# Engi301_Project_Schematic.net
KiCad netlist of a schematic drawn in EAGLE
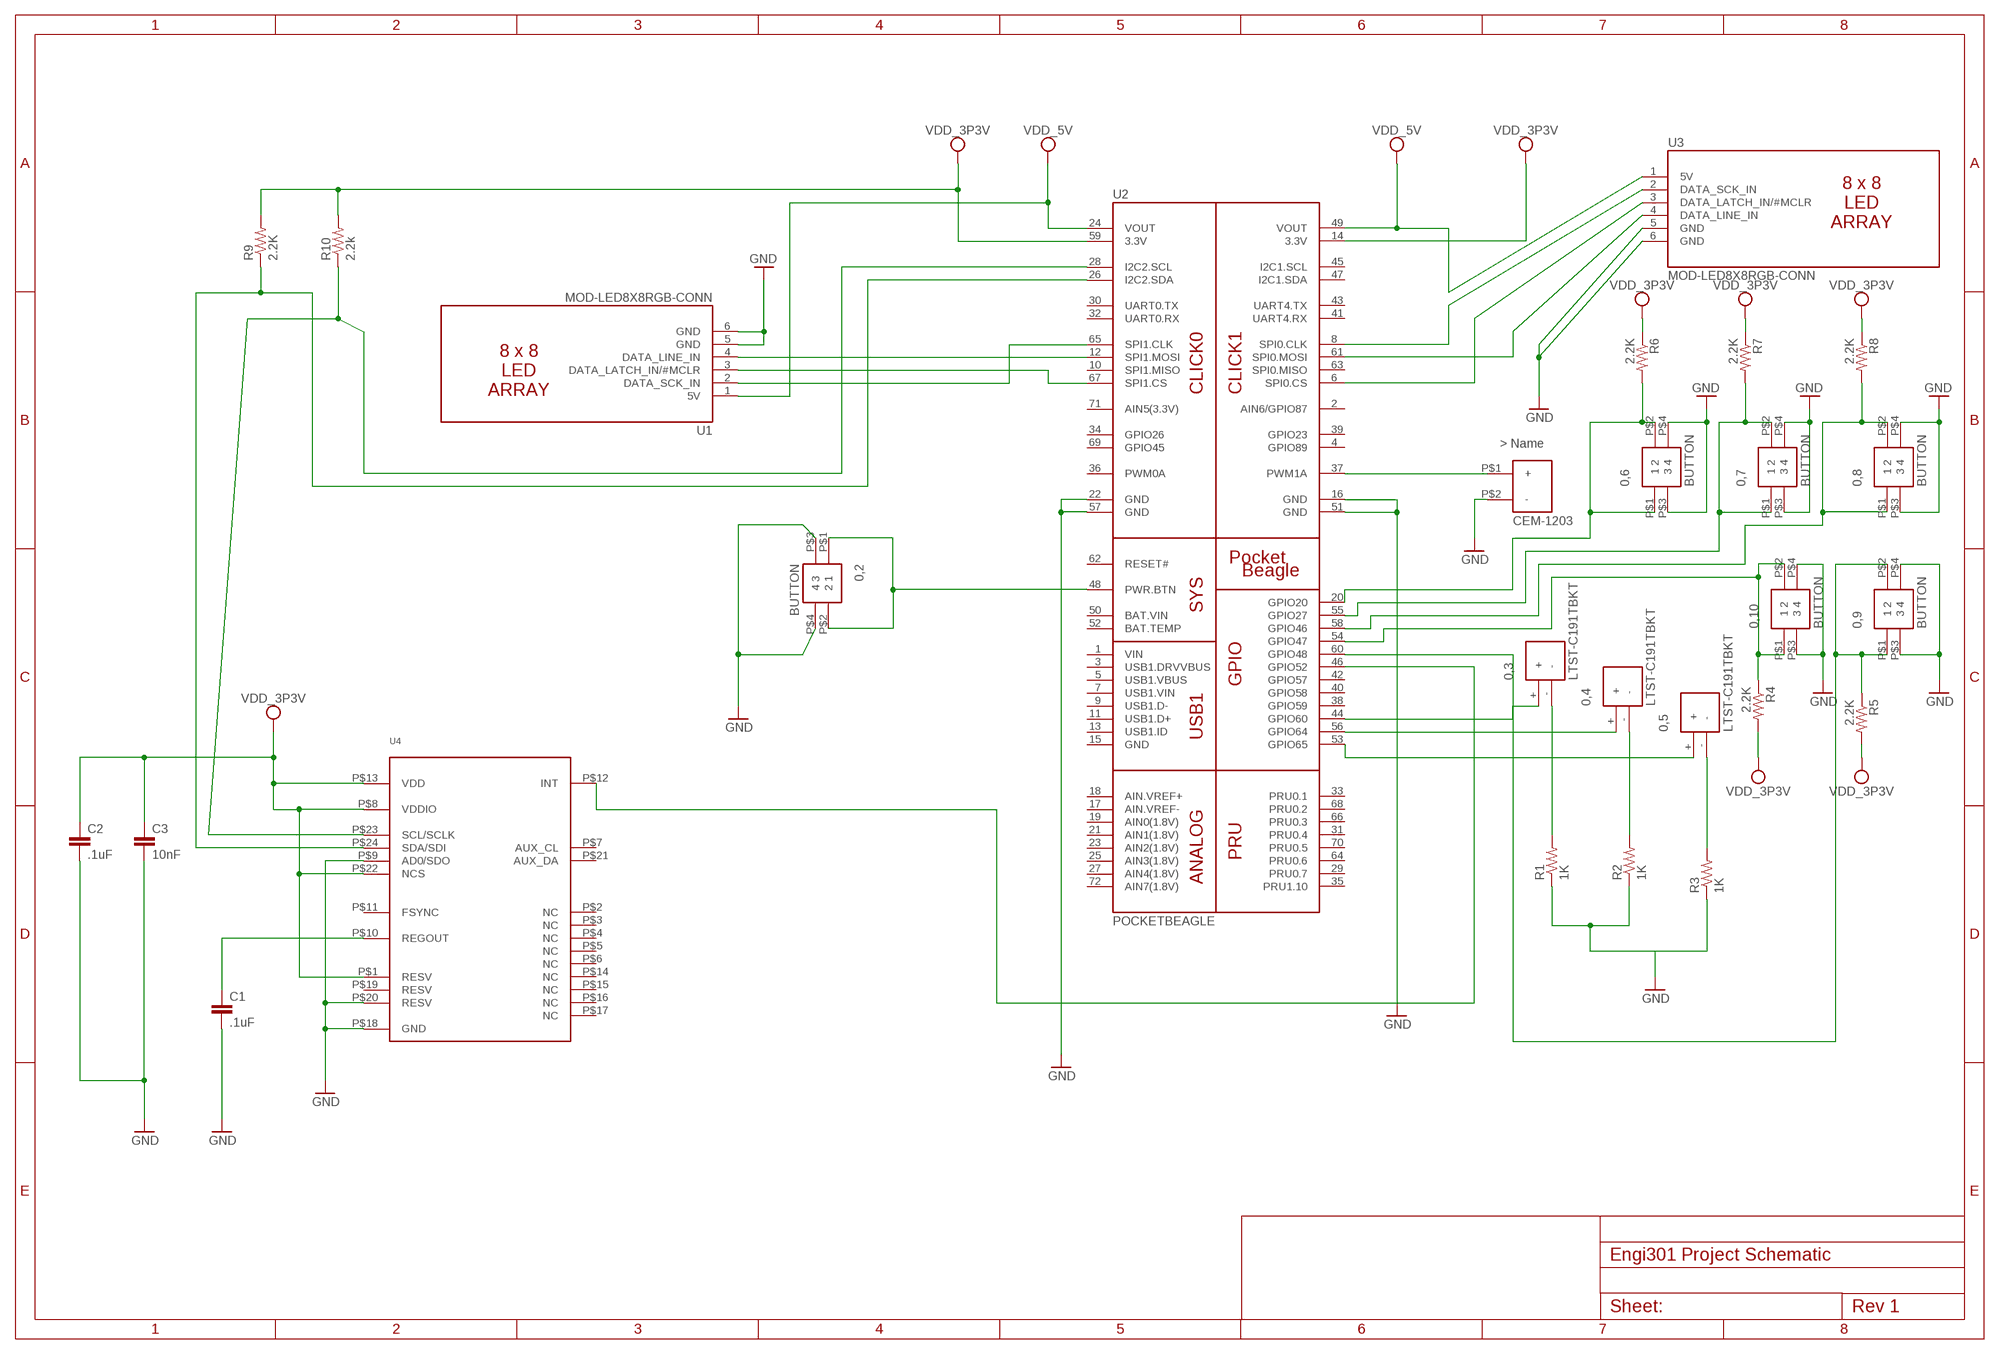
[diagram p0: schematic, sheet 1]

(export (version "E")
  (design (tool "Eeschema 10.0.6"))
  (components
    (comp (ref "0,1")
      (value "CEM-1203")
      (footprint "eagle-import:CEM-1203")
      (libsource (lib "eagle-import") (part "CEM-1203"))
    )
    (comp (ref "0,2")
      (value "BUTTON")
      (footprint "eagle-import:BUTTON")
      (libsource (lib "eagle-import") (part "BUTTON"))
    )
    (comp (ref "0,3")
      (value "LTST-C191TBKT")
      (footprint "eagle-import:LTST_C191TBKT")
      (libsource (lib "eagle-import") (part "LTST-C191TBKT"))
    )
    (comp (ref "0,4")
      (value "LTST-C191TBKT")
      (footprint "eagle-import:LTST_C191TBKT")
      (libsource (lib "eagle-import") (part "LTST-C191TBKT"))
    )
    (comp (ref "0,5")
      (value "LTST-C191TBKT")
      (footprint "eagle-import:LTST_C191TBKT")
      (libsource (lib "eagle-import") (part "LTST-C191TBKT"))
    )
    (comp (ref "0,6")
      (value "BUTTON")
      (footprint "eagle-import:BUTTON")
      (libsource (lib "eagle-import") (part "BUTTON"))
    )
    (comp (ref "0,7")
      (value "BUTTON")
      (footprint "eagle-import:BUTTON")
      (libsource (lib "eagle-import") (part "BUTTON"))
    )
    (comp (ref "0,8")
      (value "BUTTON")
      (footprint "eagle-import:BUTTON")
      (libsource (lib "eagle-import") (part "BUTTON"))
    )
    (comp (ref "0,9")
      (value "BUTTON")
      (footprint "eagle-import:BUTTON")
      (libsource (lib "eagle-import") (part "BUTTON"))
    )
    (comp (ref "0,10")
      (value "BUTTON")
      (footprint "eagle-import:BUTTON")
      (libsource (lib "eagle-import") (part "BUTTON"))
    )
    (comp (ref "C1")
      (value ".1uF")
      (footprint "eagle-import:C0603")
      (libsource (lib "eagle-import") (part "C_C0603"))
    )
    (comp (ref "C2")
      (value ".1uF")
      (footprint "eagle-import:C0603")
      (libsource (lib "eagle-import") (part "C_C0603"))
    )
    (comp (ref "C3")
      (value "10nF")
      (footprint "eagle-import:C0402")
      (libsource (lib "eagle-import") (part "C_C0402"))
    )
    (comp (ref "R1")
      (value "1K")
      (footprint "eagle-import:R0603")
      (libsource (lib "eagle-import") (part "R_R0603"))
    )
    (comp (ref "R2")
      (value "1K")
      (footprint "eagle-import:R0603")
      (libsource (lib "eagle-import") (part "R_R0603"))
    )
    (comp (ref "R3")
      (value "1K")
      (footprint "eagle-import:R0603")
      (libsource (lib "eagle-import") (part "R_R0603"))
    )
    (comp (ref "R4")
      (value "2.2K")
      (footprint "eagle-import:R0603")
      (libsource (lib "eagle-import") (part "R_R0603"))
    )
    (comp (ref "R5")
      (value "2.2K")
      (footprint "eagle-import:R0603")
      (libsource (lib "eagle-import") (part "R_R0603"))
    )
    (comp (ref "R6")
      (value "2.2K")
      (footprint "eagle-import:R0603")
      (libsource (lib "eagle-import") (part "R_R0603"))
    )
    (comp (ref "R7")
      (value "2.2K")
      (footprint "eagle-import:R0603")
      (libsource (lib "eagle-import") (part "R_R0603"))
    )
    (comp (ref "R8")
      (value "2.2K")
      (footprint "eagle-import:R0603")
      (libsource (lib "eagle-import") (part "R_R0603"))
    )
    (comp (ref "R9")
      (value "2.2K")
      (footprint "eagle-import:R0603")
      (libsource (lib "eagle-import") (part "R_R0603"))
    )
    (comp (ref "R10")
      (value "2.2k")
      (footprint "eagle-import:R0603")
      (libsource (lib "eagle-import") (part "R_R0603"))
    )
    (comp (ref "U1")
      (value "MOD-LED8X8RGB-CONN")
      (footprint "eagle-import:FE06W")
      (libsource (lib "eagle-import") (part "MOD-LED8X8RGB-CONN"))
    )
    (comp (ref "U2")
      (value "POCKETBEAGLE")
      (footprint "eagle-import:POCKETBEAGLE")
      (libsource (lib "eagle-import") (part "POCKETBEAGLE"))
    )
    (comp (ref "U3")
      (value "MOD-LED8X8RGB-CONN")
      (footprint "eagle-import:FE06W")
      (libsource (lib "eagle-import") (part "MOD-LED8X8RGB-CONN"))
    )
    (comp (ref "U4")
      (value "MPU-9250")
      (footprint "eagle-import:QFN_3MMX3MM")
      (libsource (lib "eagle-import") (part "MPU-9250"))
    )
  )
  (nets
    (net (code "1") (name "GND") (class "Default")
      (node (ref "0,1") (pin "P$2") (pinfunction "-_P$2") (pintype "bidirectional"))
      (node (ref "0,10") (pin "P$3") (pinfunction "3_P$3") (pintype "bidirectional"))
      (node (ref "0,10") (pin "P$4") (pinfunction "4_P$4") (pintype "bidirectional"))
      (node (ref "0,2") (pin "P$3") (pinfunction "3_P$3") (pintype "bidirectional"))
      (node (ref "0,2") (pin "P$4") (pinfunction "4_P$4") (pintype "bidirectional"))
      (node (ref "0,6") (pin "P$3") (pinfunction "3_P$3") (pintype "bidirectional"))
      (node (ref "0,6") (pin "P$4") (pinfunction "4_P$4") (pintype "bidirectional"))
      (node (ref "0,7") (pin "P$3") (pinfunction "3_P$3") (pintype "bidirectional"))
      (node (ref "0,7") (pin "P$4") (pinfunction "4_P$4") (pintype "bidirectional"))
      (node (ref "0,8") (pin "P$3") (pinfunction "3_P$3") (pintype "bidirectional"))
      (node (ref "0,8") (pin "P$4") (pinfunction "4_P$4") (pintype "bidirectional"))
      (node (ref "0,9") (pin "P$3") (pinfunction "3_P$3") (pintype "bidirectional"))
      (node (ref "0,9") (pin "P$4") (pinfunction "4_P$4") (pintype "bidirectional"))
      (node (ref "C1") (pin "2") (pinfunction "2_2") (pintype "passive"))
      (node (ref "C2") (pin "2") (pinfunction "2_2") (pintype "passive"))
      (node (ref "C3") (pin "2") (pinfunction "2_2") (pintype "passive"))
      (node (ref "R1") (pin "1") (pinfunction "1_1") (pintype "passive"))
      (node (ref "R2") (pin "1") (pinfunction "1_1") (pintype "passive"))
      (node (ref "R3") (pin "1") (pinfunction "1_1") (pintype "passive"))
      (node (ref "U1") (pin "5") (pinfunction "GND_5") (pintype "bidirectional"))
      (node (ref "U1") (pin "6") (pinfunction "GND_6") (pintype "bidirectional"))
      (node (ref "U2") (pin "16") (pinfunction "GND_16") (pintype "bidirectional"))
      (node (ref "U2") (pin "22") (pinfunction "GND_22") (pintype "bidirectional"))
      (node (ref "U2") (pin "51") (pinfunction "GND_51") (pintype "bidirectional"))
      (node (ref "U2") (pin "57") (pinfunction "GND_57") (pintype "bidirectional"))
      (node (ref "U3") (pin "5") (pinfunction "GND_5") (pintype "bidirectional"))
      (node (ref "U3") (pin "6") (pinfunction "GND_6") (pintype "bidirectional"))
      (node (ref "U4") (pin "P$18") (pinfunction "GND_P$18") (pintype "bidirectional"))
      (node (ref "U4") (pin "P$20") (pinfunction "RESV_P$20") (pintype "bidirectional"))
      (node (ref "U4") (pin "P$9") (pinfunction "AD0/SDO_P$9") (pintype "bidirectional"))
    )
    (net (code "2") (name "Net-(0,1-+)") (class "Default")
      (node (ref "0,1") (pin "P$1") (pinfunction "+_P$1") (pintype "bidirectional"))
      (node (ref "U2") (pin "37") (pinfunction "PWM1A_37") (pintype "bidirectional"))
    )
    (net (code "3") (name "Net-(0,2-1)") (class "Default")
      (node (ref "0,2") (pin "P$1") (pinfunction "1_P$1") (pintype "bidirectional"))
      (node (ref "0,2") (pin "P$2") (pinfunction "2_P$2") (pintype "bidirectional"))
      (node (ref "U2") (pin "48") (pinfunction "PWR.BTN_48") (pintype "bidirectional"))
    )
    (net (code "4") (name "Net-(0,3-Pad-)") (class "Default")
      (node (ref "0,3") (pin "-") (pinfunction "-_-") (pintype "bidirectional"))
      (node (ref "R1") (pin "2") (pinfunction "2_2") (pintype "passive"))
    )
    (net (code "5") (name "Net-(0,4-Pad-)") (class "Default")
      (node (ref "0,4") (pin "-") (pinfunction "-_-") (pintype "bidirectional"))
      (node (ref "R2") (pin "2") (pinfunction "2_2") (pintype "passive"))
    )
    (net (code "6") (name "Net-(0,5-Pad-)") (class "Default")
      (node (ref "0,5") (pin "-") (pinfunction "-_-") (pintype "bidirectional"))
      (node (ref "R3") (pin "2") (pinfunction "2_2") (pintype "passive"))
    )
    (net (code "7") (name "Net-(0,6-1)") (class "Default")
      (node (ref "0,6") (pin "P$1") (pinfunction "1_P$1") (pintype "bidirectional"))
      (node (ref "0,6") (pin "P$2") (pinfunction "2_P$2") (pintype "bidirectional"))
      (node (ref "R6") (pin "2") (pinfunction "2_2") (pintype "passive"))
      (node (ref "U2") (pin "20") (pinfunction "GPIO20_20") (pintype "bidirectional"))
    )
    (net (code "8") (name "Net-(0,7-1)") (class "Default")
      (node (ref "0,7") (pin "P$1") (pinfunction "1_P$1") (pintype "bidirectional"))
      (node (ref "0,7") (pin "P$2") (pinfunction "2_P$2") (pintype "bidirectional"))
      (node (ref "R7") (pin "2") (pinfunction "2_2") (pintype "passive"))
      (node (ref "U2") (pin "55") (pinfunction "GPIO27_55") (pintype "bidirectional"))
    )
    (net (code "9") (name "Net-(0,8-1)") (class "Default")
      (node (ref "0,8") (pin "P$1") (pinfunction "1_P$1") (pintype "bidirectional"))
      (node (ref "0,8") (pin "P$2") (pinfunction "2_P$2") (pintype "bidirectional"))
      (node (ref "R8") (pin "2") (pinfunction "2_2") (pintype "passive"))
      (node (ref "U2") (pin "58") (pinfunction "GPIO46_58") (pintype "bidirectional"))
    )
    (net (code "10") (name "Net-(0,9-1)") (class "Default")
      (node (ref "0,9") (pin "P$1") (pinfunction "1_P$1") (pintype "bidirectional"))
      (node (ref "0,9") (pin "P$2") (pinfunction "2_P$2") (pintype "bidirectional"))
      (node (ref "R5") (pin "1") (pinfunction "1_1") (pintype "passive"))
      (node (ref "U2") (pin "60") (pinfunction "GPIO48_60") (pintype "bidirectional"))
    )
    (net (code "11") (name "Net-(0,10-1)") (class "Default")
      (node (ref "0,10") (pin "P$1") (pinfunction "1_P$1") (pintype "bidirectional"))
      (node (ref "0,10") (pin "P$2") (pinfunction "2_P$2") (pintype "bidirectional"))
      (node (ref "R4") (pin "1") (pinfunction "1_1") (pintype "passive"))
      (node (ref "U2") (pin "54") (pinfunction "GPIO47_54") (pintype "bidirectional"))
    )
    (net (code "12") (name "Net-(U1-DATA_LATCH_IN{slash}#MCLR)") (class "Default")
      (node (ref "U1") (pin "3") (pinfunction "DATA_LATCH_IN/#MCLR_3") (pintype "bidirectional"))
      (node (ref "U2") (pin "67") (pinfunction "SPI1.CS_67") (pintype "bidirectional"))
    )
    (net (code "13") (name "Net-(U1-DATA_LINE_IN)") (class "Default")
      (node (ref "U1") (pin "4") (pinfunction "DATA_LINE_IN_4") (pintype "bidirectional"))
      (node (ref "U2") (pin "12") (pinfunction "SPI1.MOSI_12") (pintype "bidirectional"))
    )
    (net (code "14") (name "Net-(U1-DATA_SCK_IN)") (class "Default")
      (node (ref "U1") (pin "2") (pinfunction "DATA_SCK_IN_2") (pintype "bidirectional"))
      (node (ref "U2") (pin "65") (pinfunction "SPI1.CLK_65") (pintype "bidirectional"))
    )
    (net (code "15") (name "Net-(U2-GPIO52)") (class "Default")
      (node (ref "U2") (pin "46") (pinfunction "GPIO52_46") (pintype "bidirectional"))
      (node (ref "U4") (pin "P$12") (pinfunction "INT_P$12") (pintype "bidirectional"))
    )
    (net (code "16") (name "Net-(U2-GPIO60)") (class "Default")
      (node (ref "0,3") (pin "+") (pinfunction "+_+") (pintype "bidirectional"))
      (node (ref "U2") (pin "44") (pinfunction "GPIO60_44") (pintype "bidirectional"))
    )
    (net (code "17") (name "Net-(U2-GPIO64)") (class "Default")
      (node (ref "0,4") (pin "+") (pinfunction "+_+") (pintype "bidirectional"))
      (node (ref "U2") (pin "56") (pinfunction "GPIO64_56") (pintype "bidirectional"))
    )
    (net (code "18") (name "Net-(U2-GPIO65)") (class "Default")
      (node (ref "0,5") (pin "+") (pinfunction "+_+") (pintype "bidirectional"))
      (node (ref "U2") (pin "53") (pinfunction "GPIO65_53") (pintype "bidirectional"))
    )
    (net (code "19") (name "Net-(U2-I2C2.SCL)") (class "Default")
      (node (ref "R10") (pin "1") (pinfunction "1_1") (pintype "passive"))
      (node (ref "U2") (pin "28") (pinfunction "I2C2.SCL_28") (pintype "bidirectional"))
      (node (ref "U4") (pin "P$23") (pinfunction "SCL/SCLK_P$23") (pintype "bidirectional"))
    )
    (net (code "20") (name "Net-(U2-I2C2.SDA)") (class "Default")
      (node (ref "R9") (pin "1") (pinfunction "1_1") (pintype "passive"))
      (node (ref "U2") (pin "26") (pinfunction "I2C2.SDA_26") (pintype "bidirectional"))
      (node (ref "U4") (pin "P$24") (pinfunction "SDA/SDI_P$24") (pintype "bidirectional"))
    )
    (net (code "21") (name "Net-(U2-SPI0.CLK)") (class "Default")
      (node (ref "U2") (pin "8") (pinfunction "SPI0.CLK_8") (pintype "bidirectional"))
      (node (ref "U3") (pin "2") (pinfunction "DATA_SCK_IN_2") (pintype "bidirectional"))
    )
    (net (code "22") (name "Net-(U2-SPI0.CS)") (class "Default")
      (node (ref "U2") (pin "6") (pinfunction "SPI0.CS_6") (pintype "bidirectional"))
      (node (ref "U3") (pin "3") (pinfunction "DATA_LATCH_IN/#MCLR_3") (pintype "bidirectional"))
    )
    (net (code "23") (name "Net-(U2-SPI0.MOSI)") (class "Default")
      (node (ref "U2") (pin "61") (pinfunction "SPI0.MOSI_61") (pintype "bidirectional"))
      (node (ref "U3") (pin "4") (pinfunction "DATA_LINE_IN_4") (pintype "bidirectional"))
    )
    (net (code "24") (name "Net-(U4-REGOUT)") (class "Default")
      (node (ref "C1") (pin "1") (pinfunction "1_1") (pintype "passive"))
      (node (ref "U4") (pin "P$10") (pinfunction "REGOUT_P$10") (pintype "bidirectional"))
    )
    (net (code "25") (name "VDD_3P3V") (class "Default")
      (node (ref "C2") (pin "1") (pinfunction "1_1") (pintype "passive"))
      (node (ref "C3") (pin "1") (pinfunction "1_1") (pintype "passive"))
      (node (ref "R10") (pin "2") (pinfunction "2_2") (pintype "passive"))
      (node (ref "R4") (pin "2") (pinfunction "2_2") (pintype "passive"))
      (node (ref "R5") (pin "2") (pinfunction "2_2") (pintype "passive"))
      (node (ref "R6") (pin "1") (pinfunction "1_1") (pintype "passive"))
      (node (ref "R7") (pin "1") (pinfunction "1_1") (pintype "passive"))
      (node (ref "R8") (pin "1") (pinfunction "1_1") (pintype "passive"))
      (node (ref "R9") (pin "2") (pinfunction "2_2") (pintype "passive"))
      (node (ref "U2") (pin "14") (pinfunction "3.3V_14") (pintype "bidirectional"))
      (node (ref "U2") (pin "59") (pinfunction "3.3V_59") (pintype "bidirectional"))
      (node (ref "U4") (pin "P$1") (pinfunction "RESV_P$1") (pintype "bidirectional"))
      (node (ref "U4") (pin "P$13") (pinfunction "VDD_P$13") (pintype "bidirectional"))
      (node (ref "U4") (pin "P$22") (pinfunction "NCS_P$22") (pintype "bidirectional"))
      (node (ref "U4") (pin "P$8") (pinfunction "VDDIO_P$8") (pintype "bidirectional"))
    )
    (net (code "26") (name "VDD_5V") (class "Default")
      (node (ref "U1") (pin "1") (pinfunction "5V_1") (pintype "bidirectional"))
      (node (ref "U2") (pin "24") (pinfunction "VOUT_24") (pintype "bidirectional"))
      (node (ref "U2") (pin "49") (pinfunction "VOUT_49") (pintype "bidirectional"))
      (node (ref "U3") (pin "1") (pinfunction "5V_1") (pintype "bidirectional"))
    )
    (net (code "27") (name "unconnected-(U2-AIN.VREF+-Pad18)") (class "Default")
      (node (ref "U2") (pin "18") (pinfunction "AIN.VREF+_18") (pintype "bidirectional"))
    )
    (net (code "28") (name "unconnected-(U2-AIN.VREF--Pad17)") (class "Default")
      (node (ref "U2") (pin "17") (pinfunction "AIN.VREF-_17") (pintype "bidirectional"))
    )
    (net (code "29") (name "unconnected-(U2-AIN0(1.8V)-Pad19)") (class "Default")
      (node (ref "U2") (pin "19") (pinfunction "AIN0(1.8V)_19") (pintype "bidirectional"))
    )
    (net (code "30") (name "unconnected-(U2-AIN1(1.8V)-Pad21)") (class "Default")
      (node (ref "U2") (pin "21") (pinfunction "AIN1(1.8V)_21") (pintype "bidirectional"))
    )
    (net (code "31") (name "unconnected-(U2-AIN2(1.8V)-Pad23)") (class "Default")
      (node (ref "U2") (pin "23") (pinfunction "AIN2(1.8V)_23") (pintype "bidirectional"))
    )
    (net (code "32") (name "unconnected-(U2-AIN3(1.8V)-Pad25)") (class "Default")
      (node (ref "U2") (pin "25") (pinfunction "AIN3(1.8V)_25") (pintype "bidirectional"))
    )
    (net (code "33") (name "unconnected-(U2-AIN4(1.8V)-Pad27)") (class "Default")
      (node (ref "U2") (pin "27") (pinfunction "AIN4(1.8V)_27") (pintype "bidirectional"))
    )
    (net (code "34") (name "unconnected-(U2-AIN5(3.3V)-Pad71)") (class "Default")
      (node (ref "U2") (pin "71") (pinfunction "AIN5(3.3V)_71") (pintype "bidirectional"))
    )
    (net (code "35") (name "unconnected-(U2-AIN6{slash}GPIO87-Pad2)") (class "Default")
      (node (ref "U2") (pin "2") (pinfunction "AIN6/GPIO87_2") (pintype "bidirectional"))
    )
    (net (code "36") (name "unconnected-(U2-AIN7(1.8V)-Pad72)") (class "Default")
      (node (ref "U2") (pin "72") (pinfunction "AIN7(1.8V)_72") (pintype "bidirectional"))
    )
    (net (code "37") (name "unconnected-(U2-BAT.TEMP-Pad52)") (class "Default")
      (node (ref "U2") (pin "52") (pinfunction "BAT.TEMP_52") (pintype "bidirectional"))
    )
    (net (code "38") (name "unconnected-(U2-BAT.VIN-Pad50)") (class "Default")
      (node (ref "U2") (pin "50") (pinfunction "BAT.VIN_50") (pintype "bidirectional"))
    )
    (net (code "39") (name "unconnected-(U2-GND-Pad15)") (class "Default")
      (node (ref "U2") (pin "15") (pinfunction "GND_15") (pintype "bidirectional"))
    )
    (net (code "40") (name "unconnected-(U2-GPIO23-Pad39)") (class "Default")
      (node (ref "U2") (pin "39") (pinfunction "GPIO23_39") (pintype "bidirectional"))
    )
    (net (code "41") (name "unconnected-(U2-GPIO26-Pad34)") (class "Default")
      (node (ref "U2") (pin "34") (pinfunction "GPIO26_34") (pintype "bidirectional"))
    )
    (net (code "42") (name "unconnected-(U2-GPIO45-Pad69)") (class "Default")
      (node (ref "U2") (pin "69") (pinfunction "GPIO45_69") (pintype "bidirectional"))
    )
    (net (code "43") (name "unconnected-(U2-GPIO57-Pad42)") (class "Default")
      (node (ref "U2") (pin "42") (pinfunction "GPIO57_42") (pintype "bidirectional"))
    )
    (net (code "44") (name "unconnected-(U2-GPIO58-Pad40)") (class "Default")
      (node (ref "U2") (pin "40") (pinfunction "GPIO58_40") (pintype "bidirectional"))
    )
    (net (code "45") (name "unconnected-(U2-GPIO59-Pad38)") (class "Default")
      (node (ref "U2") (pin "38") (pinfunction "GPIO59_38") (pintype "bidirectional"))
    )
    (net (code "46") (name "unconnected-(U2-GPIO89-Pad4)") (class "Default")
      (node (ref "U2") (pin "4") (pinfunction "GPIO89_4") (pintype "bidirectional"))
    )
    (net (code "47") (name "unconnected-(U2-I2C1.SCL-Pad45)") (class "Default")
      (node (ref "U2") (pin "45") (pinfunction "I2C1.SCL_45") (pintype "bidirectional"))
    )
    (net (code "48") (name "unconnected-(U2-I2C1.SDA-Pad47)") (class "Default")
      (node (ref "U2") (pin "47") (pinfunction "I2C1.SDA_47") (pintype "bidirectional"))
    )
    (net (code "49") (name "unconnected-(U2-PRU0.1-Pad33)") (class "Default")
      (node (ref "U2") (pin "33") (pinfunction "PRU0.1_33") (pintype "bidirectional"))
    )
    (net (code "50") (name "unconnected-(U2-PRU0.2-Pad68)") (class "Default")
      (node (ref "U2") (pin "68") (pinfunction "PRU0.2_68") (pintype "bidirectional"))
    )
    (net (code "51") (name "unconnected-(U2-PRU0.3-Pad66)") (class "Default")
      (node (ref "U2") (pin "66") (pinfunction "PRU0.3_66") (pintype "bidirectional"))
    )
    (net (code "52") (name "unconnected-(U2-PRU0.4-Pad31)") (class "Default")
      (node (ref "U2") (pin "31") (pinfunction "PRU0.4_31") (pintype "bidirectional"))
    )
    (net (code "53") (name "unconnected-(U2-PRU0.5-Pad70)") (class "Default")
      (node (ref "U2") (pin "70") (pinfunction "PRU0.5_70") (pintype "bidirectional"))
    )
    (net (code "54") (name "unconnected-(U2-PRU0.6-Pad64)") (class "Default")
      (node (ref "U2") (pin "64") (pinfunction "PRU0.6_64") (pintype "bidirectional"))
    )
    (net (code "55") (name "unconnected-(U2-PRU0.7-Pad29)") (class "Default")
      (node (ref "U2") (pin "29") (pinfunction "PRU0.7_29") (pintype "bidirectional"))
    )
    (net (code "56") (name "unconnected-(U2-PRU1.10-Pad35)") (class "Default")
      (node (ref "U2") (pin "35") (pinfunction "PRU1.10_35") (pintype "bidirectional"))
    )
    (net (code "57") (name "unconnected-(U2-PWM0A-Pad36)") (class "Default")
      (node (ref "U2") (pin "36") (pinfunction "PWM0A_36") (pintype "bidirectional"))
    )
    (net (code "58") (name "unconnected-(U2-RESET#-Pad62)") (class "Default")
      (node (ref "U2") (pin "62") (pinfunction "RESET#_62") (pintype "bidirectional"))
    )
    (net (code "59") (name "unconnected-(U2-SPI0.MISO-Pad63)") (class "Default")
      (node (ref "U2") (pin "63") (pinfunction "SPI0.MISO_63") (pintype "bidirectional"))
    )
    (net (code "60") (name "unconnected-(U2-SPI1.MISO-Pad10)") (class "Default")
      (node (ref "U2") (pin "10") (pinfunction "SPI1.MISO_10") (pintype "bidirectional"))
    )
    (net (code "61") (name "unconnected-(U2-UART0.RX-Pad32)") (class "Default")
      (node (ref "U2") (pin "32") (pinfunction "UART0.RX_32") (pintype "bidirectional"))
    )
    (net (code "62") (name "unconnected-(U2-UART0.TX-Pad30)") (class "Default")
      (node (ref "U2") (pin "30") (pinfunction "UART0.TX_30") (pintype "bidirectional"))
    )
    (net (code "63") (name "unconnected-(U2-UART4.RX-Pad41)") (class "Default")
      (node (ref "U2") (pin "41") (pinfunction "UART4.RX_41") (pintype "bidirectional"))
    )
    (net (code "64") (name "unconnected-(U2-UART4.TX-Pad43)") (class "Default")
      (node (ref "U2") (pin "43") (pinfunction "UART4.TX_43") (pintype "bidirectional"))
    )
    (net (code "65") (name "unconnected-(U2-USB1.D+-Pad11)") (class "Default")
      (node (ref "U2") (pin "11") (pinfunction "USB1.D+_11") (pintype "bidirectional"))
    )
    (net (code "66") (name "unconnected-(U2-USB1.D--Pad9)") (class "Default")
      (node (ref "U2") (pin "9") (pinfunction "USB1.D-_9") (pintype "bidirectional"))
    )
    (net (code "67") (name "unconnected-(U2-USB1.DRVVBUS-Pad3)") (class "Default")
      (node (ref "U2") (pin "3") (pinfunction "USB1.DRVVBUS_3") (pintype "bidirectional"))
    )
    (net (code "68") (name "unconnected-(U2-USB1.ID-Pad13)") (class "Default")
      (node (ref "U2") (pin "13") (pinfunction "USB1.ID_13") (pintype "bidirectional"))
    )
    (net (code "69") (name "unconnected-(U2-USB1.VBUS-Pad5)") (class "Default")
      (node (ref "U2") (pin "5") (pinfunction "USB1.VBUS_5") (pintype "bidirectional"))
    )
    (net (code "70") (name "unconnected-(U2-USB1.VIN-Pad7)") (class "Default")
      (node (ref "U2") (pin "7") (pinfunction "USB1.VIN_7") (pintype "bidirectional"))
    )
    (net (code "71") (name "unconnected-(U2-VIN-Pad1)") (class "Default")
      (node (ref "U2") (pin "1") (pinfunction "VIN_1") (pintype "bidirectional"))
    )
    (net (code "72") (name "unconnected-(U4-AUX_CL-PadP$7)") (class "Default")
      (node (ref "U4") (pin "P$7") (pinfunction "AUX_CL_P$7") (pintype "bidirectional"))
    )
    (net (code "73") (name "unconnected-(U4-AUX_DA-PadP$21)") (class "Default")
      (node (ref "U4") (pin "P$21") (pinfunction "AUX_DA_P$21") (pintype "bidirectional"))
    )
    (net (code "74") (name "unconnected-(U4-FSYNC-PadP$11)") (class "Default")
      (node (ref "U4") (pin "P$11") (pinfunction "FSYNC_P$11") (pintype "bidirectional"))
    )
    (net (code "75") (name "unconnected-(U4-NC-PadP$2)") (class "Default")
      (node (ref "U4") (pin "P$2") (pinfunction "NC_P$2") (pintype "bidirectional"))
    )
    (net (code "76") (name "unconnected-(U4-NC-PadP$3)") (class "Default")
      (node (ref "U4") (pin "P$3") (pinfunction "NC_P$3") (pintype "bidirectional"))
    )
    (net (code "77") (name "unconnected-(U4-NC-PadP$4)") (class "Default")
      (node (ref "U4") (pin "P$4") (pinfunction "NC_P$4") (pintype "bidirectional"))
    )
    (net (code "78") (name "unconnected-(U4-NC-PadP$5)") (class "Default")
      (node (ref "U4") (pin "P$5") (pinfunction "NC_P$5") (pintype "bidirectional"))
    )
    (net (code "79") (name "unconnected-(U4-NC-PadP$6)") (class "Default")
      (node (ref "U4") (pin "P$6") (pinfunction "NC_P$6") (pintype "bidirectional"))
    )
    (net (code "80") (name "unconnected-(U4-NC-PadP$14)") (class "Default")
      (node (ref "U4") (pin "P$14") (pinfunction "NC_P$14") (pintype "bidirectional"))
    )
    (net (code "81") (name "unconnected-(U4-NC-PadP$15)") (class "Default")
      (node (ref "U4") (pin "P$15") (pinfunction "NC_P$15") (pintype "bidirectional"))
    )
    (net (code "82") (name "unconnected-(U4-NC-PadP$16)") (class "Default")
      (node (ref "U4") (pin "P$16") (pinfunction "NC_P$16") (pintype "bidirectional"))
    )
    (net (code "83") (name "unconnected-(U4-NC-PadP$17)") (class "Default")
      (node (ref "U4") (pin "P$17") (pinfunction "NC_P$17") (pintype "bidirectional"))
    )
    (net (code "84") (name "unconnected-(U4-RESV-PadP$19)") (class "Default")
      (node (ref "U4") (pin "P$19") (pinfunction "RESV_P$19") (pintype "bidirectional"))
    )
  )
)
